# RF.net
KiCad netlist of a schematic drawn in Altium Designer
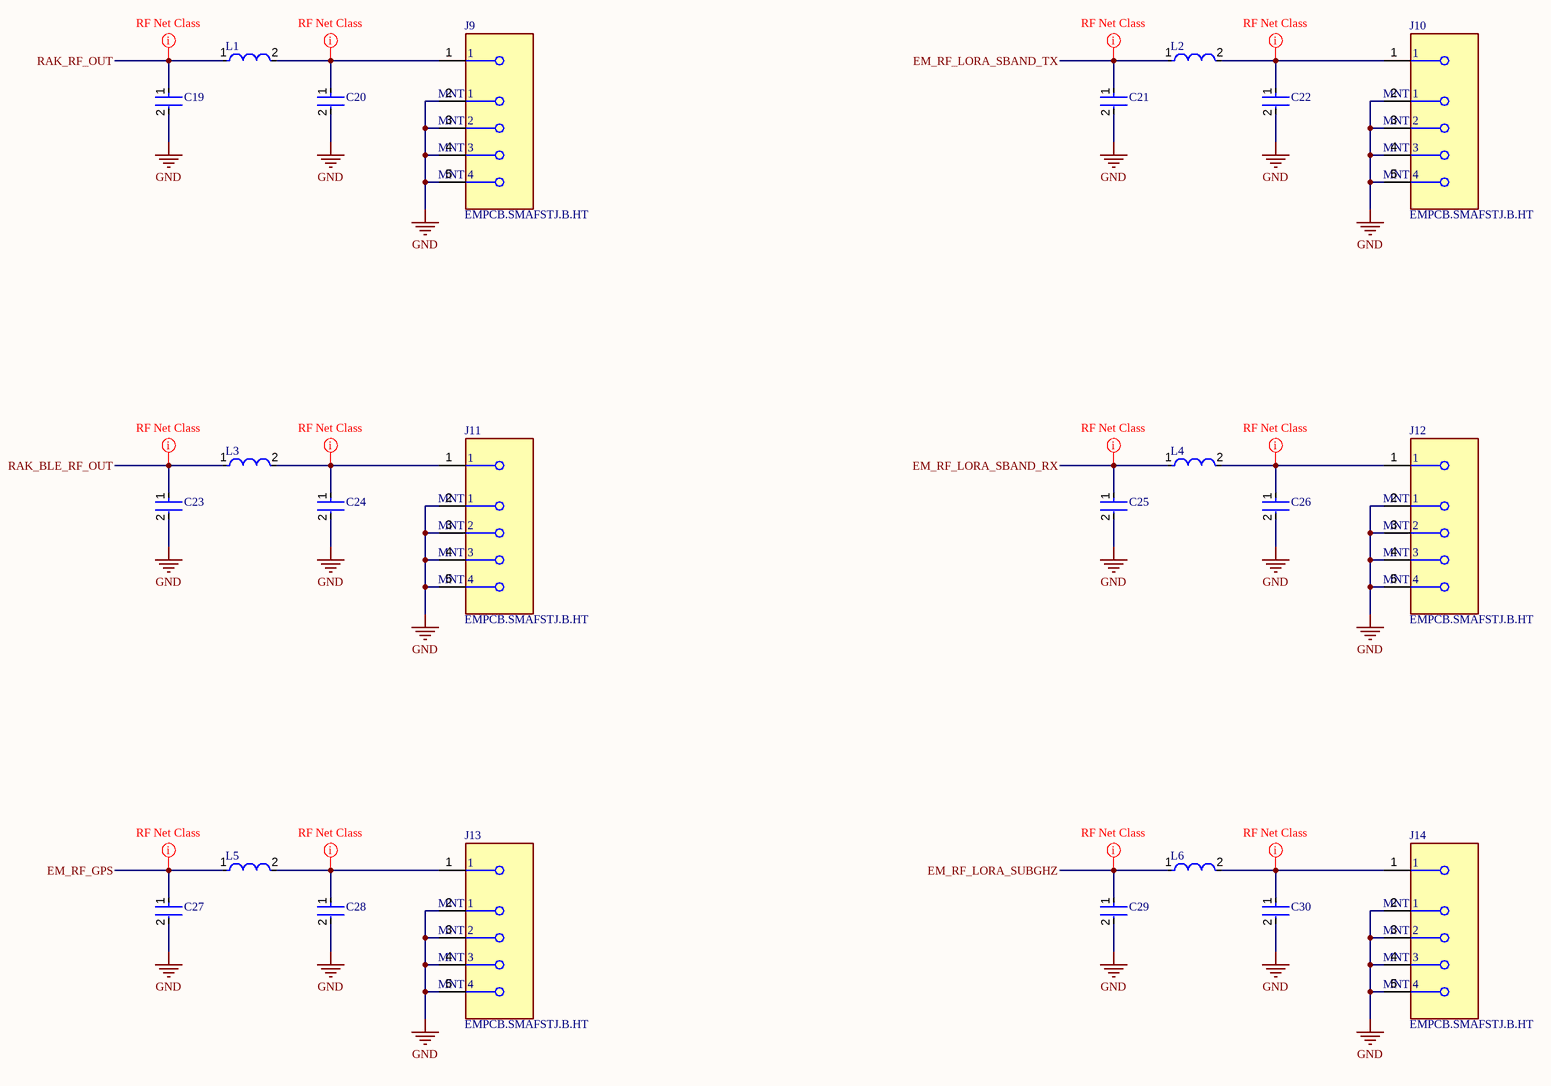
[diagram p0: RF.SchDoc]

(export (version "E")
  (design (tool "Eeschema 10.0.6"))
  (components
    (comp (ref "C19")
      (value "GJM1555C1H5R0CB01D")
      (footprint "FP-GJM155-0_05-MFG")
      (description "Multi-Layer Ceramic Capacitor 5pF C0G  ±0.25pF 0402 Paper T/R")
      (libsource (lib "Altium Content Vault") (part "02cd4be3c70576c341d710602a673aa"))
    )
    (comp (ref "C20")
      (value "GJM1555C1H5R0CB01D")
      (footprint "FP-GJM155-0_05-MFG")
      (description "Multi-Layer Ceramic Capacitor 5pF C0G  ±0.25pF 0402 Paper T/R")
      (libsource (lib "Altium Content Vault") (part "02cd4be3c70576c341d710602a673aa"))
    )
    (comp (ref "C21")
      (value "GJM1555C1H5R0CB01D")
      (footprint "FP-GJM155-0_05-MFG")
      (description "Multi-Layer Ceramic Capacitor 5pF C0G  ±0.25pF 0402 Paper T/R")
      (libsource (lib "Altium Content Vault") (part "02cd4be3c70576c341d710602a673aa"))
    )
    (comp (ref "C22")
      (value "GJM1555C1H5R0CB01D")
      (footprint "FP-GJM155-0_05-MFG")
      (description "Multi-Layer Ceramic Capacitor 5pF C0G  ±0.25pF 0402 Paper T/R")
      (libsource (lib "Altium Content Vault") (part "02cd4be3c70576c341d710602a673aa"))
    )
    (comp (ref "C23")
      (value "GJM1555C1H5R0CB01D")
      (footprint "FP-GJM155-0_05-MFG")
      (description "Multi-Layer Ceramic Capacitor 5pF C0G  ±0.25pF 0402 Paper T/R")
      (libsource (lib "Altium Content Vault") (part "02cd4be3c70576c341d710602a673aa"))
    )
    (comp (ref "C24")
      (value "GJM1555C1H5R0CB01D")
      (footprint "FP-GJM155-0_05-MFG")
      (description "Multi-Layer Ceramic Capacitor 5pF C0G  ±0.25pF 0402 Paper T/R")
      (libsource (lib "Altium Content Vault") (part "02cd4be3c70576c341d710602a673aa"))
    )
    (comp (ref "C25")
      (value "GJM1555C1H5R0CB01D")
      (footprint "FP-GJM155-0_05-MFG")
      (description "Multi-Layer Ceramic Capacitor 5pF C0G  ±0.25pF 0402 Paper T/R")
      (libsource (lib "Altium Content Vault") (part "02cd4be3c70576c341d710602a673aa"))
    )
    (comp (ref "C26")
      (value "GJM1555C1H5R0CB01D")
      (footprint "FP-GJM155-0_05-MFG")
      (description "Multi-Layer Ceramic Capacitor 5pF C0G  ±0.25pF 0402 Paper T/R")
      (libsource (lib "Altium Content Vault") (part "02cd4be3c70576c341d710602a673aa"))
    )
    (comp (ref "C27")
      (value "GJM1555C1H5R0CB01D")
      (footprint "FP-GJM155-0_05-MFG")
      (description "Multi-Layer Ceramic Capacitor 5pF C0G  ±0.25pF 0402 Paper T/R")
      (libsource (lib "Altium Content Vault") (part "02cd4be3c70576c341d710602a673aa"))
    )
    (comp (ref "C28")
      (value "GJM1555C1H5R0CB01D")
      (footprint "FP-GJM155-0_05-MFG")
      (description "Multi-Layer Ceramic Capacitor 5pF C0G  ±0.25pF 0402 Paper T/R")
      (libsource (lib "Altium Content Vault") (part "02cd4be3c70576c341d710602a673aa"))
    )
    (comp (ref "C29")
      (value "GJM1555C1H5R0CB01D")
      (footprint "FP-GJM155-0_05-MFG")
      (description "Multi-Layer Ceramic Capacitor 5pF C0G  ±0.25pF 0402 Paper T/R")
      (libsource (lib "Altium Content Vault") (part "02cd4be3c70576c341d710602a673aa"))
    )
    (comp (ref "C30")
      (value "GJM1555C1H5R0CB01D")
      (footprint "FP-GJM155-0_05-MFG")
      (description "Multi-Layer Ceramic Capacitor 5pF C0G  ±0.25pF 0402 Paper T/R")
      (libsource (lib "Altium Content Vault") (part "02cd4be3c70576c341d710602a673aa"))
    )
    (comp (ref "J9")
      (value "EMPCB.SMAFSTJ.B.HT")
      (footprint "FP-EMPCB_SMAFSTJ_B_HT-MFG")
      (description "CONN SMA JACK STR 50OHM EDGE MNT")
      (fields
        (field (name "OCTOPART") "https://octopart.com/empcb.smafstj.b.ht-taoglas-24204431")
        (field (name "MANUFACTURER") "Taoglas Limited")
      )
      (libsource (lib "Altium Content Vault") (part "c65b8a639cdaef1819ea20b5466f8fa"))
    )
    (comp (ref "J10")
      (value "EMPCB.SMAFSTJ.B.HT")
      (footprint "FP-EMPCB_SMAFSTJ_B_HT-MFG")
      (description "CONN SMA JACK STR 50OHM EDGE MNT")
      (fields
        (field (name "OCTOPART") "https://octopart.com/empcb.smafstj.b.ht-taoglas-24204431")
        (field (name "MANUFACTURER") "Taoglas Limited")
      )
      (libsource (lib "Altium Content Vault") (part "c65b8a639cdaef1819ea20b5466f8fa"))
    )
    (comp (ref "J11")
      (value "EMPCB.SMAFSTJ.B.HT")
      (footprint "FP-EMPCB_SMAFSTJ_B_HT-MFG")
      (description "CONN SMA JACK STR 50OHM EDGE MNT")
      (fields
        (field (name "OCTOPART") "https://octopart.com/empcb.smafstj.b.ht-taoglas-24204431")
        (field (name "MANUFACTURER") "Taoglas Limited")
      )
      (libsource (lib "Altium Content Vault") (part "c65b8a639cdaef1819ea20b5466f8fa"))
    )
    (comp (ref "J12")
      (value "EMPCB.SMAFSTJ.B.HT")
      (footprint "FP-EMPCB_SMAFSTJ_B_HT-MFG")
      (description "CONN SMA JACK STR 50OHM EDGE MNT")
      (fields
        (field (name "OCTOPART") "https://octopart.com/empcb.smafstj.b.ht-taoglas-24204431")
        (field (name "MANUFACTURER") "Taoglas Limited")
      )
      (libsource (lib "Altium Content Vault") (part "c65b8a639cdaef1819ea20b5466f8fa"))
    )
    (comp (ref "J13")
      (value "EMPCB.SMAFSTJ.B.HT")
      (footprint "FP-EMPCB_SMAFSTJ_B_HT-MFG")
      (description "CONN SMA JACK STR 50OHM EDGE MNT")
      (fields
        (field (name "OCTOPART") "https://octopart.com/empcb.smafstj.b.ht-taoglas-24204431")
        (field (name "MANUFACTURER") "Taoglas Limited")
      )
      (libsource (lib "Altium Content Vault") (part "c65b8a639cdaef1819ea20b5466f8fa"))
    )
    (comp (ref "J14")
      (value "EMPCB.SMAFSTJ.B.HT")
      (footprint "FP-EMPCB_SMAFSTJ_B_HT-MFG")
      (description "CONN SMA JACK STR 50OHM EDGE MNT")
      (fields
        (field (name "OCTOPART") "https://octopart.com/empcb.smafstj.b.ht-taoglas-24204431")
        (field (name "MANUFACTURER") "Taoglas Limited")
      )
      (libsource (lib "Altium Content Vault") (part "c65b8a639cdaef1819ea20b5466f8fa"))
    )
    (comp (ref "L1")
      (value "LQW15AN2N9D00D")
      (footprint "FP-LQW15AN_00-W0_6-0_1-MFG")
      (description "Wire Wound RF Inductor 2.9nH ±0.5nH 750mA 0.07Ω 0402 (1005)")
      (libsource (lib "Altium Content Vault") (part "725321dda6339637d4d059423bc1c3c"))
    )
    (comp (ref "L2")
      (value "LQW15AN2N9D00D")
      (footprint "FP-LQW15AN_00-W0_6-0_1-MFG")
      (description "Wire Wound RF Inductor 2.9nH ±0.5nH 750mA 0.07Ω 0402 (1005)")
      (libsource (lib "Altium Content Vault") (part "725321dda6339637d4d059423bc1c3c"))
    )
    (comp (ref "L3")
      (value "LQW15AN2N9D00D")
      (footprint "FP-LQW15AN_00-W0_6-0_1-MFG")
      (description "Wire Wound RF Inductor 2.9nH ±0.5nH 750mA 0.07Ω 0402 (1005)")
      (libsource (lib "Altium Content Vault") (part "725321dda6339637d4d059423bc1c3c"))
    )
    (comp (ref "L4")
      (value "LQW15AN2N9D00D")
      (footprint "FP-LQW15AN_00-W0_6-0_1-MFG")
      (description "Wire Wound RF Inductor 2.9nH ±0.5nH 750mA 0.07Ω 0402 (1005)")
      (libsource (lib "Altium Content Vault") (part "725321dda6339637d4d059423bc1c3c"))
    )
    (comp (ref "L5")
      (value "LQW15AN2N9D00D")
      (footprint "FP-LQW15AN_00-W0_6-0_1-MFG")
      (description "Wire Wound RF Inductor 2.9nH ±0.5nH 750mA 0.07Ω 0402 (1005)")
      (libsource (lib "Altium Content Vault") (part "725321dda6339637d4d059423bc1c3c"))
    )
    (comp (ref "L6")
      (value "LQW15AN2N9D00D")
      (footprint "FP-LQW15AN_00-W0_6-0_1-MFG")
      (description "Wire Wound RF Inductor 2.9nH ±0.5nH 750mA 0.07Ω 0402 (1005)")
      (libsource (lib "Altium Content Vault") (part "725321dda6339637d4d059423bc1c3c"))
    )
  )
  (nets
    (net (code "1") (name "/EM_RF_GPS") (class "Default")
      (node (ref "C27") (pin "1") (pinfunction "1_1") (pintype "passive"))
      (node (ref "L5") (pin "1") (pinfunction "1_1") (pintype "passive"))
    )
    (net (code "2") (name "/EM_RF_LORA_SBAND_RX") (class "Default")
      (node (ref "C25") (pin "1") (pinfunction "1_1") (pintype "passive"))
      (node (ref "L4") (pin "1") (pinfunction "1_1") (pintype "passive"))
    )
    (net (code "3") (name "/EM_RF_LORA_SBAND_TX") (class "Default")
      (node (ref "C21") (pin "1") (pinfunction "1_1") (pintype "passive"))
      (node (ref "L2") (pin "1") (pinfunction "1_1") (pintype "passive"))
    )
    (net (code "4") (name "/EM_RF_LORA_SUBGHZ") (class "Default")
      (node (ref "C29") (pin "1") (pinfunction "1_1") (pintype "passive"))
      (node (ref "L6") (pin "1") (pinfunction "1_1") (pintype "passive"))
    )
    (net (code "5") (name "/RAK_BLE_RF_OUT") (class "Default")
      (node (ref "C23") (pin "1") (pinfunction "1_1") (pintype "passive"))
      (node (ref "L3") (pin "1") (pinfunction "1_1") (pintype "passive"))
    )
    (net (code "6") (name "/RAK_RF_OUT") (class "Default")
      (node (ref "C19") (pin "1") (pinfunction "1_1") (pintype "passive"))
      (node (ref "L1") (pin "1") (pinfunction "1_1") (pintype "passive"))
    )
    (net (code "7") (name "GND") (class "Default")
      (node (ref "C19") (pin "2") (pinfunction "2_2") (pintype "passive"))
      (node (ref "C20") (pin "2") (pinfunction "2_2") (pintype "passive"))
      (node (ref "C21") (pin "2") (pinfunction "2_2") (pintype "passive"))
      (node (ref "C22") (pin "2") (pinfunction "2_2") (pintype "passive"))
      (node (ref "C23") (pin "2") (pinfunction "2_2") (pintype "passive"))
      (node (ref "C24") (pin "2") (pinfunction "2_2") (pintype "passive"))
      (node (ref "C25") (pin "2") (pinfunction "2_2") (pintype "passive"))
      (node (ref "C26") (pin "2") (pinfunction "2_2") (pintype "passive"))
      (node (ref "C27") (pin "2") (pinfunction "2_2") (pintype "passive"))
      (node (ref "C28") (pin "2") (pinfunction "2_2") (pintype "passive"))
      (node (ref "C29") (pin "2") (pinfunction "2_2") (pintype "passive"))
      (node (ref "C30") (pin "2") (pinfunction "2_2") (pintype "passive"))
      (node (ref "J10") (pin "2") (pinfunction "MNT_1_2") (pintype "passive"))
      (node (ref "J10") (pin "3") (pinfunction "MNT_2_3") (pintype "passive"))
      (node (ref "J10") (pin "4") (pinfunction "MNT_3_4") (pintype "passive"))
      (node (ref "J10") (pin "5") (pinfunction "MNT_4_5") (pintype "passive"))
      (node (ref "J11") (pin "2") (pinfunction "MNT_1_2") (pintype "passive"))
      (node (ref "J11") (pin "3") (pinfunction "MNT_2_3") (pintype "passive"))
      (node (ref "J11") (pin "4") (pinfunction "MNT_3_4") (pintype "passive"))
      (node (ref "J11") (pin "5") (pinfunction "MNT_4_5") (pintype "passive"))
      (node (ref "J12") (pin "2") (pinfunction "MNT_1_2") (pintype "passive"))
      (node (ref "J12") (pin "3") (pinfunction "MNT_2_3") (pintype "passive"))
      (node (ref "J12") (pin "4") (pinfunction "MNT_3_4") (pintype "passive"))
      (node (ref "J12") (pin "5") (pinfunction "MNT_4_5") (pintype "passive"))
      (node (ref "J13") (pin "2") (pinfunction "MNT_1_2") (pintype "passive"))
      (node (ref "J13") (pin "3") (pinfunction "MNT_2_3") (pintype "passive"))
      (node (ref "J13") (pin "4") (pinfunction "MNT_3_4") (pintype "passive"))
      (node (ref "J13") (pin "5") (pinfunction "MNT_4_5") (pintype "passive"))
      (node (ref "J14") (pin "2") (pinfunction "MNT_1_2") (pintype "passive"))
      (node (ref "J14") (pin "3") (pinfunction "MNT_2_3") (pintype "passive"))
      (node (ref "J14") (pin "4") (pinfunction "MNT_3_4") (pintype "passive"))
      (node (ref "J14") (pin "5") (pinfunction "MNT_4_5") (pintype "passive"))
      (node (ref "J9") (pin "2") (pinfunction "MNT_1_2") (pintype "passive"))
      (node (ref "J9") (pin "3") (pinfunction "MNT_2_3") (pintype "passive"))
      (node (ref "J9") (pin "4") (pinfunction "MNT_3_4") (pintype "passive"))
      (node (ref "J9") (pin "5") (pinfunction "MNT_4_5") (pintype "passive"))
    )
    (net (code "8") (name "Net-(C20-Pad1)") (class "Default")
      (node (ref "C20") (pin "1") (pinfunction "1_1") (pintype "passive"))
      (node (ref "J9") (pin "1") (pinfunction "1_1") (pintype "passive"))
      (node (ref "L1") (pin "2") (pinfunction "2_2") (pintype "passive"))
    )
    (net (code "9") (name "Net-(C22-Pad1)") (class "Default")
      (node (ref "C22") (pin "1") (pinfunction "1_1") (pintype "passive"))
      (node (ref "J10") (pin "1") (pinfunction "1_1") (pintype "passive"))
      (node (ref "L2") (pin "2") (pinfunction "2_2") (pintype "passive"))
    )
    (net (code "10") (name "Net-(C24-Pad1)") (class "Default")
      (node (ref "C24") (pin "1") (pinfunction "1_1") (pintype "passive"))
      (node (ref "J11") (pin "1") (pinfunction "1_1") (pintype "passive"))
      (node (ref "L3") (pin "2") (pinfunction "2_2") (pintype "passive"))
    )
    (net (code "11") (name "Net-(C26-Pad1)") (class "Default")
      (node (ref "C26") (pin "1") (pinfunction "1_1") (pintype "passive"))
      (node (ref "J12") (pin "1") (pinfunction "1_1") (pintype "passive"))
      (node (ref "L4") (pin "2") (pinfunction "2_2") (pintype "passive"))
    )
    (net (code "12") (name "Net-(C28-Pad1)") (class "Default")
      (node (ref "C28") (pin "1") (pinfunction "1_1") (pintype "passive"))
      (node (ref "J13") (pin "1") (pinfunction "1_1") (pintype "passive"))
      (node (ref "L5") (pin "2") (pinfunction "2_2") (pintype "passive"))
    )
    (net (code "13") (name "Net-(C30-Pad1)") (class "Default")
      (node (ref "C30") (pin "1") (pinfunction "1_1") (pintype "passive"))
      (node (ref "J14") (pin "1") (pinfunction "1_1") (pintype "passive"))
      (node (ref "L6") (pin "2") (pinfunction "2_2") (pintype "passive"))
    )
  )
)
